# apple_all_pt1.net
KiCad netlist of a schematic drawn in EAGLE
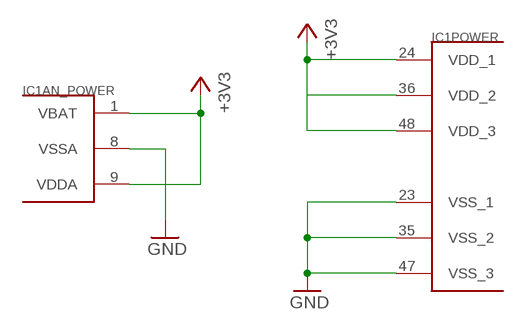
[diagram p0: schematic, sheet 1, part 1 of 2]
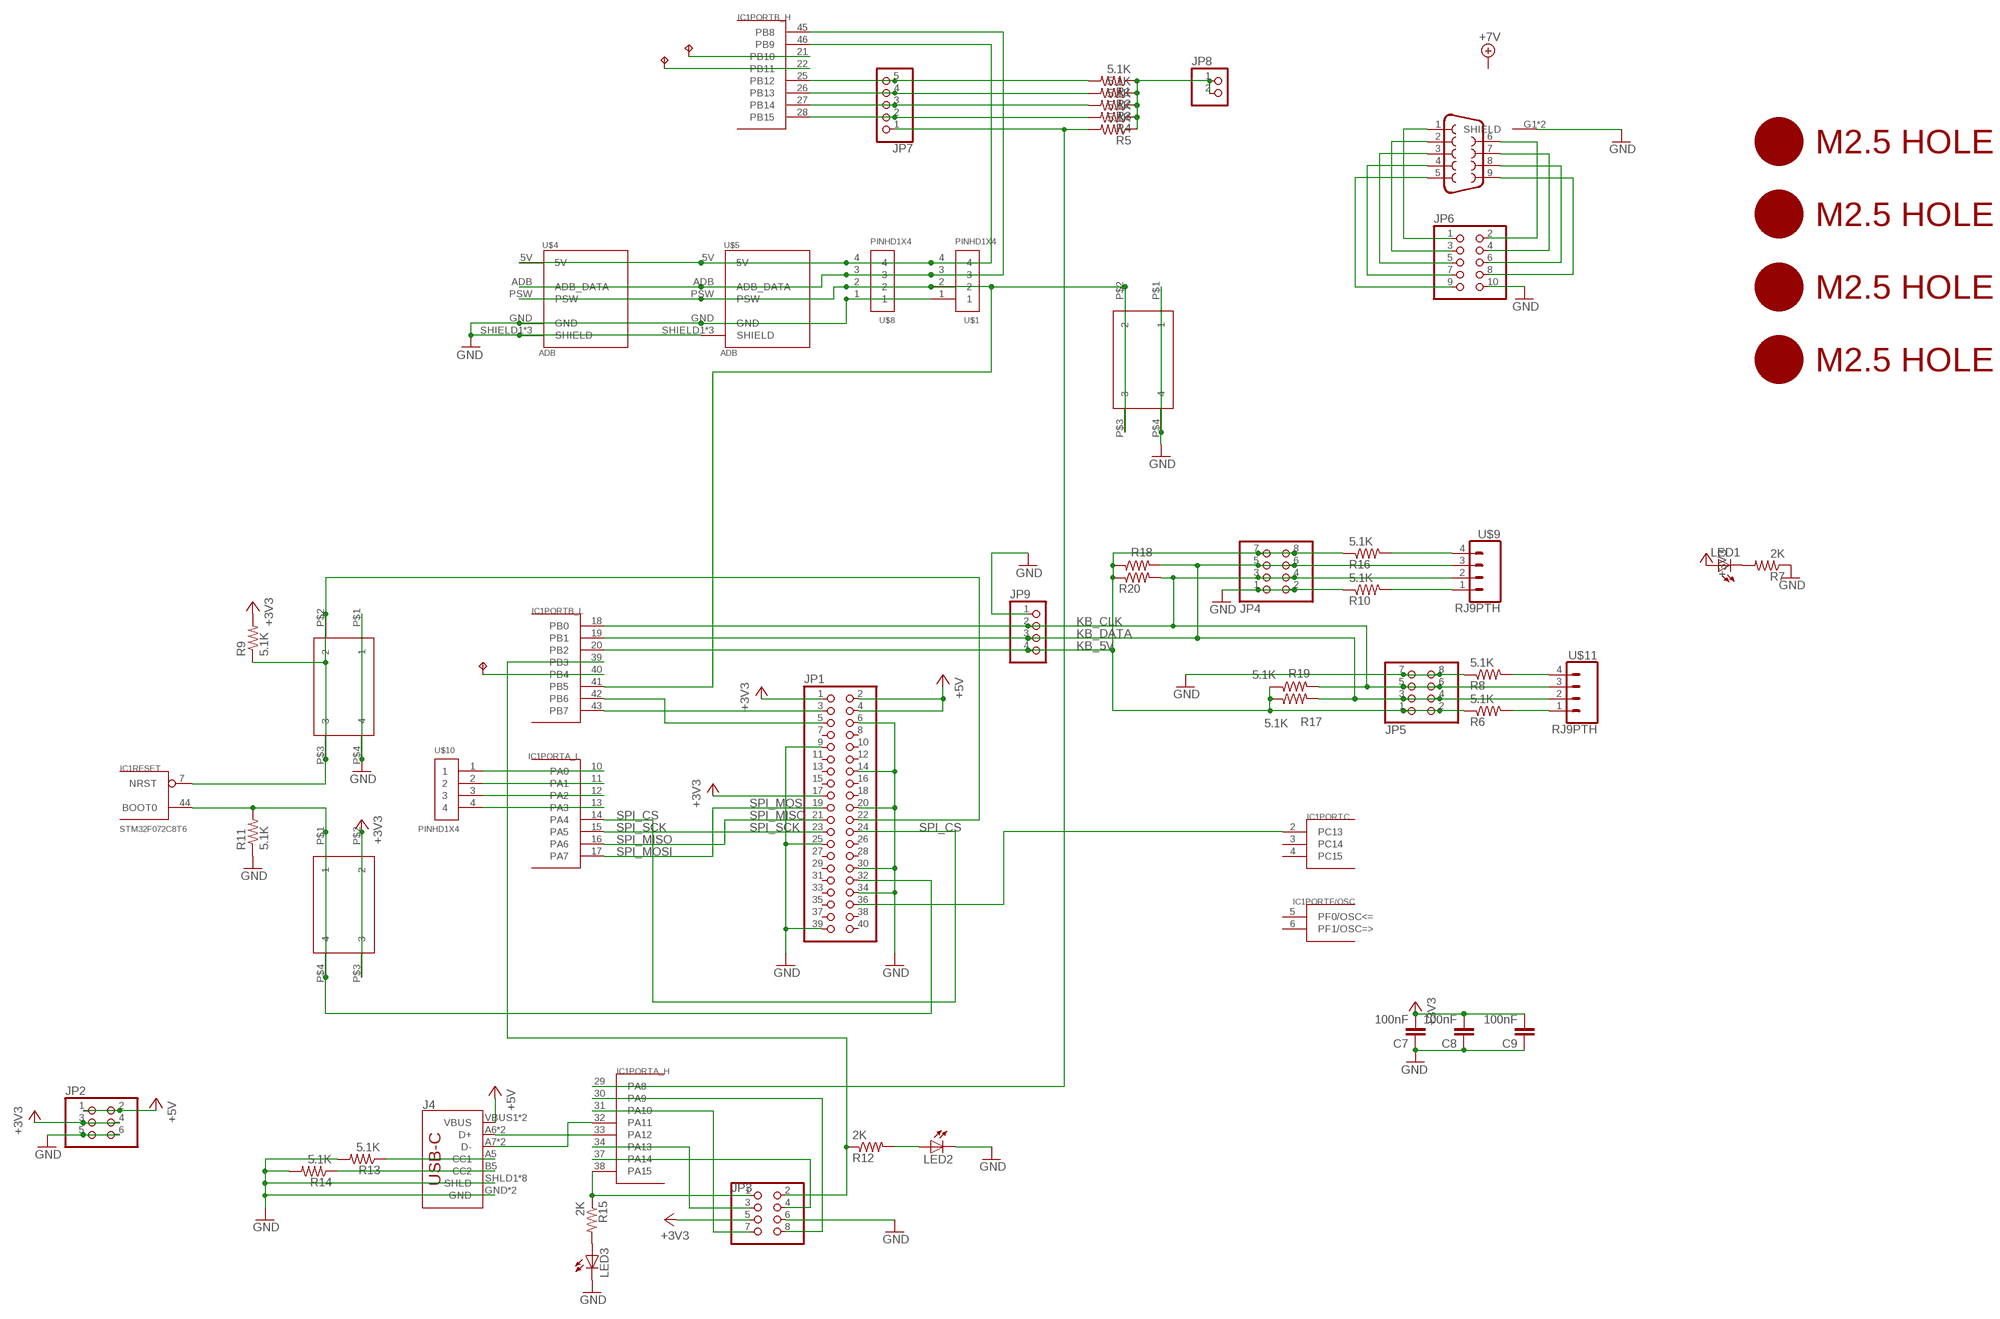
[diagram p1: schematic, sheet 1, part 2 of 2]

(export (version "E")
  (design (tool "Eeschema 10.0.6"))
  (components
    (comp (ref "C7")
      (value "100nF")
      (footprint "eagle-import:0805@1")
      (libsource (lib "eagle-import") (part "CAP0805"))
    )
    (comp (ref "C8")
      (value "100nF")
      (footprint "eagle-import:0805@1")
      (libsource (lib "eagle-import") (part "CAP0805"))
    )
    (comp (ref "C9")
      (value "100nF")
      (footprint "eagle-import:0805@1")
      (libsource (lib "eagle-import") (part "CAP0805"))
    )
    (comp (ref "IC1")
      (value "STM32F072C8T6")
      (footprint "eagle-import:TQFP48")
      (libsource (lib "eagle-import") (part "STM32F072C8T6"))
    )
    (comp (ref "J2")
      (value "DB9FEMALE")
      (footprint "eagle-import:DB9")
      (libsource (lib "eagle-import") (part "DB9FEMALE"))
    )
    (comp (ref "J4")
      (value "USB_C16PIN")
      (footprint "eagle-import:USB-C-16P")
      (libsource (lib "eagle-import") (part "USB_C16PIN"))
    )
    (comp (ref "JP1")
      (value "PINHD-2X20-BIG")
      (footprint "eagle-import:2X20-BIG")
      (libsource (lib "eagle-import") (part "PINHD-2X20-BIG"))
    )
    (comp (ref "JP2")
      (value "PINHD-2X3")
      (footprint "eagle-import:2X03")
      (libsource (lib "eagle-import") (part "PINHD-2X3"))
    )
    (comp (ref "JP3")
      (value "PINHD-2X4")
      (footprint "eagle-import:2X04")
      (libsource (lib "eagle-import") (part "PINHD-2X4"))
    )
    (comp (ref "JP4")
      (value "PINHD-2X4")
      (footprint "eagle-import:2X04")
      (libsource (lib "eagle-import") (part "PINHD-2X4"))
    )
    (comp (ref "JP5")
      (value "PINHD-2X4")
      (footprint "eagle-import:2X04")
      (libsource (lib "eagle-import") (part "PINHD-2X4"))
    )
    (comp (ref "JP6")
      (value "PINHD-2X5")
      (footprint "eagle-import:2X05")
      (libsource (lib "eagle-import") (part "PINHD-2X5"))
    )
    (comp (ref "JP7")
      (value "PINHD-1X5")
      (footprint "eagle-import:1X05")
      (libsource (lib "eagle-import") (part "PINHD-1X5"))
    )
    (comp (ref "JP8")
      (value "PINHD-1X2")
      (footprint "eagle-import:1X02")
      (libsource (lib "eagle-import") (part "PINHD-1X2"))
    )
    (comp (ref "JP9")
      (value "PINHD-1X4")
      (footprint "eagle-import:1X04")
      (libsource (lib "eagle-import") (part "PINHD-1X4"))
    )
    (comp (ref "LED1")
      (value "LEDCHIP-LED0805")
      (footprint "eagle-import:CHIP-LED0805")
      (libsource (lib "eagle-import") (part "LEDCHIP-LED0805"))
    )
    (comp (ref "LED2")
      (value "LEDCHIP-LED0805")
      (footprint "eagle-import:CHIP-LED0805")
      (libsource (lib "eagle-import") (part "LEDCHIP-LED0805"))
    )
    (comp (ref "LED3")
      (value "LEDCHIP-LED0805")
      (footprint "eagle-import:CHIP-LED0805")
      (libsource (lib "eagle-import") (part "LEDCHIP-LED0805"))
    )
    (comp (ref "R1")
      (value "5.1K")
      (footprint "eagle-import:0805")
      (libsource (lib "eagle-import") (part "RESISTOR0805-RES"))
    )
    (comp (ref "R2")
      (value "5.1K")
      (footprint "eagle-import:0805")
      (libsource (lib "eagle-import") (part "RESISTOR0805-RES"))
    )
    (comp (ref "R3")
      (value "5.1K")
      (footprint "eagle-import:0805")
      (libsource (lib "eagle-import") (part "RESISTOR0805-RES"))
    )
    (comp (ref "R4")
      (value "5.1K")
      (footprint "eagle-import:0805")
      (libsource (lib "eagle-import") (part "RESISTOR0805-RES"))
    )
    (comp (ref "R5")
      (value "5.1K")
      (footprint "eagle-import:0805")
      (libsource (lib "eagle-import") (part "RESISTOR0805-RES"))
    )
    (comp (ref "R6")
      (value "5.1K")
      (footprint "eagle-import:0805")
      (libsource (lib "eagle-import") (part "RESISTOR0805-RES"))
    )
    (comp (ref "R7")
      (value "2K")
      (footprint "eagle-import:0805")
      (libsource (lib "eagle-import") (part "RESISTOR0805-RES"))
    )
    (comp (ref "R8")
      (value "5.1K")
      (footprint "eagle-import:0805")
      (libsource (lib "eagle-import") (part "RESISTOR0805-RES"))
    )
    (comp (ref "R9")
      (value "5.1K")
      (footprint "eagle-import:0805")
      (libsource (lib "eagle-import") (part "RESISTOR0805-RES"))
    )
    (comp (ref "R10")
      (value "5.1K")
      (footprint "eagle-import:0805")
      (libsource (lib "eagle-import") (part "RESISTOR0805-RES"))
    )
    (comp (ref "R11")
      (value "5.1K")
      (footprint "eagle-import:0805")
      (libsource (lib "eagle-import") (part "RESISTOR0805-RES"))
    )
    (comp (ref "R12")
      (value "2K")
      (footprint "eagle-import:0805")
      (libsource (lib "eagle-import") (part "RESISTOR0805-RES"))
    )
    (comp (ref "R13")
      (value "5.1K")
      (footprint "eagle-import:0805")
      (libsource (lib "eagle-import") (part "RESISTOR0805-RES"))
    )
    (comp (ref "R14")
      (value "5.1K")
      (footprint "eagle-import:0805")
      (libsource (lib "eagle-import") (part "RESISTOR0805-RES"))
    )
    (comp (ref "R15")
      (value "2K")
      (footprint "eagle-import:0805")
      (libsource (lib "eagle-import") (part "RESISTOR0805-RES"))
    )
    (comp (ref "R16")
      (value "5.1K")
      (footprint "eagle-import:0805")
      (libsource (lib "eagle-import") (part "RESISTOR0805-RES"))
    )
    (comp (ref "R17")
      (value "5.1K")
      (footprint "eagle-import:0805")
      (libsource (lib "eagle-import") (part "RESISTOR0805-RES"))
    )
    (comp (ref "R18")
      (value "5.1K")
      (footprint "eagle-import:0805")
      (libsource (lib "eagle-import") (part "RESISTOR0805-RES"))
    )
    (comp (ref "R19")
      (value "5.1K")
      (footprint "eagle-import:0805")
      (libsource (lib "eagle-import") (part "RESISTOR0805-RES"))
    )
    (comp (ref "R20")
      (value "5.1K")
      (footprint "eagle-import:0805")
      (libsource (lib "eagle-import") (part "RESISTOR0805-RES"))
    )
    (comp (ref "SW1")
      (value "324_SW")
      (footprint "eagle-import:342_SWICH_FOOT")
      (libsource (lib "eagle-import") (part "324_SW"))
    )
    (comp (ref "SW2")
      (value "324_SW")
      (footprint "eagle-import:342_SWICH_FOOT")
      (libsource (lib "eagle-import") (part "324_SW"))
    )
    (comp (ref "SW3")
      (value "324_SW")
      (footprint "eagle-import:342_SWICH_FOOT")
      (libsource (lib "eagle-import") (part "324_SW"))
    )
    (comp (ref "TP1")
      (value "TPTP12R")
      (footprint "eagle-import:TP12R")
      (libsource (lib "eagle-import") (part "TPTP12R"))
    )
    (comp (ref "TP2")
      (value "TPTP12R")
      (footprint "eagle-import:TP12R")
      (libsource (lib "eagle-import") (part "TPTP12R"))
    )
    (comp (ref "TP3")
      (value "TPTP12R")
      (footprint "eagle-import:TP12R")
      (libsource (lib "eagle-import") (part "TPTP12R"))
    )
    (comp (ref "U$1")
      (value "PINHD1X4")
      (footprint "eagle-import:1X04-CLEANBIG")
      (libsource (lib "eagle-import") (part "PINHD1X4"))
    )
    (comp (ref "U$2")
      (value "M2.5HOLE")
      (footprint "eagle-import:M2.5HOLE")
      (libsource (lib "eagle-import") (part "M2.5HOLE"))
    )
    (comp (ref "U$3")
      (value "M2.5HOLE")
      (footprint "eagle-import:M2.5HOLE")
      (libsource (lib "eagle-import") (part "M2.5HOLE"))
    )
    (comp (ref "U$4")
      (value "ADB")
      (footprint "eagle-import:DIN4")
      (libsource (lib "eagle-import") (part "ADB"))
    )
    (comp (ref "U$5")
      (value "ADB")
      (footprint "eagle-import:DIN4")
      (libsource (lib "eagle-import") (part "ADB"))
    )
    (comp (ref "U$6")
      (value "M2.5HOLE")
      (footprint "eagle-import:M2.5HOLE")
      (libsource (lib "eagle-import") (part "M2.5HOLE"))
    )
    (comp (ref "U$7")
      (value "M2.5HOLE")
      (footprint "eagle-import:M2.5HOLE")
      (libsource (lib "eagle-import") (part "M2.5HOLE"))
    )
    (comp (ref "U$8")
      (value "PINHD1X4")
      (footprint "eagle-import:1X04-CLEANBIG")
      (libsource (lib "eagle-import") (part "PINHD1X4"))
    )
    (comp (ref "U$9")
      (value "RJ9PTH")
      (footprint "eagle-import:RJ9")
      (libsource (lib "eagle-import") (part "RJ9PTH"))
    )
    (comp (ref "U$10")
      (value "PINHD1X4")
      (footprint "eagle-import:1X04-CLEANBIG")
      (libsource (lib "eagle-import") (part "PINHD1X4"))
    )
    (comp (ref "U$11")
      (value "RJ9PTH")
      (footprint "eagle-import:RJ9")
      (libsource (lib "eagle-import") (part "RJ9PTH"))
    )
  )
  (nets
    (net (code "1") (name "+3V3") (class "Default")
      (node (ref "C7") (pin "2") (pinfunction "2_2") (pintype "passive"))
      (node (ref "C8") (pin "2") (pinfunction "2_2") (pintype "passive"))
      (node (ref "C9") (pin "2") (pinfunction "2_2") (pintype "passive"))
      (node (ref "IC1") (pin "1") (pinfunction "VBAT_1") (pintype "power_in"))
      (node (ref "IC1") (pin "24") (pinfunction "VDD_1_24") (pintype "power_in"))
      (node (ref "IC1") (pin "36") (pinfunction "VDD_2_36") (pintype "power_in"))
      (node (ref "IC1") (pin "48") (pinfunction "VDD_3_48") (pintype "power_in"))
      (node (ref "IC1") (pin "9") (pinfunction "VDDA_9") (pintype "power_in"))
      (node (ref "JP1") (pin "1") (pinfunction "1_1") (pintype "passive"))
      (node (ref "JP1") (pin "17") (pinfunction "17_17") (pintype "passive"))
      (node (ref "JP2") (pin "3") (pinfunction "3_3") (pintype "passive"))
      (node (ref "JP2") (pin "4") (pinfunction "4_4") (pintype "passive"))
      (node (ref "JP3") (pin "5") (pinfunction "5_5") (pintype "passive"))
      (node (ref "LED1") (pin "A") (pinfunction "A_A") (pintype "passive"))
      (node (ref "R9") (pin "2") (pinfunction "2_2") (pintype "passive"))
      (node (ref "SW2") (pin "P$2") (pinfunction "2_P$2") (pintype "bidirectional"))
      (node (ref "SW2") (pin "P$3") (pinfunction "3_P$3") (pintype "bidirectional"))
    )
    (net (code "2") (name "+5V") (class "Default")
      (node (ref "J4") (pin "VBUS1") (pinfunction "VBUS_VBUS1") (pintype "bidirectional"))
      (node (ref "J4") (pin "VBUS2") (pinfunction "VBUS_VBUS2") (pintype "bidirectional"))
      (node (ref "JP1") (pin "2") (pinfunction "2_2") (pintype "passive"))
      (node (ref "JP1") (pin "4") (pinfunction "4_4") (pintype "passive"))
      (node (ref "JP2") (pin "1") (pinfunction "1_1") (pintype "passive"))
      (node (ref "JP2") (pin "2") (pinfunction "2_2") (pintype "passive"))
    )
    (net (code "4") (name "/KB_5V") (class "Default")
      (node (ref "IC1") (pin "20") (pinfunction "PB2_20") (pintype "bidirectional"))
      (node (ref "JP4") (pin "7") (pinfunction "7_7") (pintype "passive"))
      (node (ref "JP4") (pin "8") (pinfunction "8_8") (pintype "passive"))
      (node (ref "JP5") (pin "1") (pinfunction "1_1") (pintype "passive"))
      (node (ref "JP5") (pin "2") (pinfunction "2_2") (pintype "passive"))
      (node (ref "JP9") (pin "4") (pinfunction "4_4") (pintype "passive"))
      (node (ref "R16") (pin "1") (pinfunction "1_1") (pintype "passive"))
      (node (ref "R17") (pin "1") (pinfunction "1_1") (pintype "passive"))
      (node (ref "R18") (pin "1") (pinfunction "1_1") (pintype "passive"))
      (node (ref "R19") (pin "1") (pinfunction "1_1") (pintype "passive"))
      (node (ref "R20") (pin "1") (pinfunction "1_1") (pintype "passive"))
      (node (ref "R6") (pin "1") (pinfunction "1_1") (pintype "passive"))
    )
    (net (code "5") (name "/KB_CLK") (class "Default")
      (node (ref "IC1") (pin "18") (pinfunction "PB0_18") (pintype "bidirectional"))
      (node (ref "JP4") (pin "3") (pinfunction "3_3") (pintype "passive"))
      (node (ref "JP4") (pin "4") (pinfunction "4_4") (pintype "passive"))
      (node (ref "JP5") (pin "5") (pinfunction "5_5") (pintype "passive"))
      (node (ref "JP5") (pin "6") (pinfunction "6_6") (pintype "passive"))
      (node (ref "JP9") (pin "2") (pinfunction "2_2") (pintype "passive"))
      (node (ref "R19") (pin "2") (pinfunction "2_2") (pintype "passive"))
      (node (ref "R20") (pin "2") (pinfunction "2_2") (pintype "passive"))
      (node (ref "U$11") (pin "3") (pinfunction "3_3") (pintype "passive"))
      (node (ref "U$9") (pin "2") (pinfunction "2_2") (pintype "passive"))
    )
    (net (code "6") (name "/KB_DATA") (class "Default")
      (node (ref "IC1") (pin "19") (pinfunction "PB1_19") (pintype "bidirectional"))
      (node (ref "JP4") (pin "5") (pinfunction "5_5") (pintype "passive"))
      (node (ref "JP4") (pin "6") (pinfunction "6_6") (pintype "passive"))
      (node (ref "JP5") (pin "3") (pinfunction "3_3") (pintype "passive"))
      (node (ref "JP5") (pin "4") (pinfunction "4_4") (pintype "passive"))
      (node (ref "JP9") (pin "3") (pinfunction "3_3") (pintype "passive"))
      (node (ref "R17") (pin "2") (pinfunction "2_2") (pintype "passive"))
      (node (ref "R18") (pin "2") (pinfunction "2_2") (pintype "passive"))
      (node (ref "U$11") (pin "2") (pinfunction "2_2") (pintype "passive"))
      (node (ref "U$9") (pin "3") (pinfunction "3_3") (pintype "passive"))
    )
    (net (code "7") (name "/SPI_CS") (class "Default")
      (node (ref "IC1") (pin "14") (pinfunction "PA4_14") (pintype "bidirectional"))
      (node (ref "JP1") (pin "24") (pinfunction "24_24") (pintype "passive"))
    )
    (net (code "8") (name "/SPI_MISO") (class "Default")
      (node (ref "IC1") (pin "16") (pinfunction "PA6_16") (pintype "bidirectional"))
      (node (ref "JP1") (pin "21") (pinfunction "21_21") (pintype "passive"))
    )
    (net (code "9") (name "/SPI_MOSI") (class "Default")
      (node (ref "IC1") (pin "17") (pinfunction "PA7_17") (pintype "bidirectional"))
      (node (ref "JP1") (pin "19") (pinfunction "19_19") (pintype "passive"))
    )
    (net (code "10") (name "/SPI_SCK") (class "Default")
      (node (ref "IC1") (pin "15") (pinfunction "PA5_15") (pintype "bidirectional"))
      (node (ref "JP1") (pin "23") (pinfunction "23_23") (pintype "passive"))
    )
    (net (code "11") (name "GND") (class "Default")
      (node (ref "C7") (pin "1") (pinfunction "1_1") (pintype "passive"))
      (node (ref "C8") (pin "1") (pinfunction "1_1") (pintype "passive"))
      (node (ref "C9") (pin "1") (pinfunction "1_1") (pintype "passive"))
      (node (ref "IC1") (pin "23") (pinfunction "VSS_1_23") (pintype "power_in"))
      (node (ref "IC1") (pin "35") (pinfunction "VSS_2_35") (pintype "power_in"))
      (node (ref "IC1") (pin "47") (pinfunction "VSS_3_47") (pintype "power_in"))
      (node (ref "IC1") (pin "8") (pinfunction "VSSA_8") (pintype "power_in"))
      (node (ref "J2") (pin "G1") (pinfunction "SHIELD_G1") (pintype "bidirectional"))
      (node (ref "J2") (pin "G2") (pinfunction "SHIELD_G2") (pintype "bidirectional"))
      (node (ref "J4") (pin "GND") (pinfunction "GND_GND") (pintype "bidirectional"))
      (node (ref "J4") (pin "GND2") (pinfunction "GND_GND2") (pintype "bidirectional"))
      (node (ref "J4") (pin "SHLD1") (pinfunction "SHLD_SHLD1") (pintype "bidirectional"))
      (node (ref "J4") (pin "SHLD2") (pinfunction "SHLD_SHLD2") (pintype "bidirectional"))
      (node (ref "J4") (pin "SHLD3") (pinfunction "SHLD_SHLD3") (pintype "bidirectional"))
      (node (ref "J4") (pin "SHLD4") (pinfunction "SHLD_SHLD4") (pintype "bidirectional"))
      (node (ref "J4") (pin "SHLD5") (pinfunction "SHLD_SHLD5") (pintype "bidirectional"))
      (node (ref "J4") (pin "SHLD6") (pinfunction "SHLD_SHLD6") (pintype "bidirectional"))
      (node (ref "J4") (pin "SHLD7") (pinfunction "SHLD_SHLD7") (pintype "bidirectional"))
      (node (ref "J4") (pin "SHLD8") (pinfunction "SHLD_SHLD8") (pintype "bidirectional"))
      (node (ref "JP1") (pin "14") (pinfunction "14_14") (pintype "passive"))
      (node (ref "JP1") (pin "20") (pinfunction "20_20") (pintype "passive"))
      (node (ref "JP1") (pin "25") (pinfunction "25_25") (pintype "passive"))
      (node (ref "JP1") (pin "30") (pinfunction "30_30") (pintype "passive"))
      (node (ref "JP1") (pin "34") (pinfunction "34_34") (pintype "passive"))
      (node (ref "JP1") (pin "39") (pinfunction "39_39") (pintype "passive"))
      (node (ref "JP1") (pin "6") (pinfunction "6_6") (pintype "passive"))
      (node (ref "JP1") (pin "9") (pinfunction "9_9") (pintype "passive"))
      (node (ref "JP2") (pin "5") (pinfunction "5_5") (pintype "passive"))
      (node (ref "JP2") (pin "6") (pinfunction "6_6") (pintype "passive"))
      (node (ref "JP3") (pin "6") (pinfunction "6_6") (pintype "passive"))
      (node (ref "JP4") (pin "1") (pinfunction "1_1") (pintype "passive"))
      (node (ref "JP4") (pin "2") (pinfunction "2_2") (pintype "passive"))
      (node (ref "JP5") (pin "7") (pinfunction "7_7") (pintype "passive"))
      (node (ref "JP5") (pin "8") (pinfunction "8_8") (pintype "passive"))
      (node (ref "JP6") (pin "10") (pinfunction "10_10") (pintype "passive"))
      (node (ref "JP9") (pin "1") (pinfunction "1_1") (pintype "passive"))
      (node (ref "LED2") (pin "C") (pinfunction "C_C") (pintype "passive"))
      (node (ref "LED3") (pin "C") (pinfunction "C_C") (pintype "passive"))
      (node (ref "R10") (pin "1") (pinfunction "1_1") (pintype "passive"))
      (node (ref "R11") (pin "1") (pinfunction "1_1") (pintype "passive"))
      (node (ref "R13") (pin "2") (pinfunction "2_2") (pintype "passive"))
      (node (ref "R14") (pin "2") (pinfunction "2_2") (pintype "passive"))
      (node (ref "R7") (pin "1") (pinfunction "1_1") (pintype "passive"))
      (node (ref "R8") (pin "1") (pinfunction "1_1") (pintype "passive"))
      (node (ref "SW1") (pin "P$1") (pinfunction "1_P$1") (pintype "bidirectional"))
      (node (ref "SW1") (pin "P$4") (pinfunction "4_P$4") (pintype "bidirectional"))
      (node (ref "SW3") (pin "P$1") (pinfunction "1_P$1") (pintype "bidirectional"))
      (node (ref "SW3") (pin "P$4") (pinfunction "4_P$4") (pintype "bidirectional"))
      (node (ref "U$1") (pin "1") (pinfunction "1_1") (pintype "bidirectional"))
      (node (ref "U$4") (pin "GND") (pinfunction "GND_GND") (pintype "bidirectional"))
      (node (ref "U$4") (pin "SHIELD1") (pinfunction "SHIELD_SHIELD1") (pintype "bidirectional"))
      (node (ref "U$4") (pin "SHIELD2") (pinfunction "SHIELD_SHIELD2") (pintype "bidirectional"))
      (node (ref "U$4") (pin "SHIELD3") (pinfunction "SHIELD_SHIELD3") (pintype "bidirectional"))
      (node (ref "U$5") (pin "GND") (pinfunction "GND_GND") (pintype "bidirectional"))
      (node (ref "U$5") (pin "SHIELD1") (pinfunction "SHIELD_SHIELD1") (pintype "bidirectional"))
      (node (ref "U$5") (pin "SHIELD2") (pinfunction "SHIELD_SHIELD2") (pintype "bidirectional"))
      (node (ref "U$5") (pin "SHIELD3") (pinfunction "SHIELD_SHIELD3") (pintype "bidirectional"))
      (node (ref "U$8") (pin "1") (pinfunction "1_1") (pintype "bidirectional"))
    )
    (net (code "12") (name "Net-(IC1B-PA8)") (class "Default")
      (node (ref "IC1") (pin "29") (pinfunction "PA8_29") (pintype "bidirectional"))
      (node (ref "JP7") (pin "1") (pinfunction "1_1") (pintype "passive"))
      (node (ref "R5") (pin "2") (pinfunction "2_2") (pintype "passive"))
    )
    (net (code "13") (name "Net-(IC1B-PA9)") (class "Default")
      (node (ref "IC1") (pin "30") (pinfunction "PA9_30") (pintype "bidirectional"))
      (node (ref "JP3") (pin "8") (pinfunction "8_8") (pintype "passive"))
    )
    (net (code "14") (name "Net-(IC1B-PA10)") (class "Default")
      (node (ref "IC1") (pin "31") (pinfunction "PA10_31") (pintype "bidirectional"))
      (node (ref "JP3") (pin "7") (pinfunction "7_7") (pintype "passive"))
    )
    (net (code "15") (name "Net-(IC1B-PA11)") (class "Default")
      (node (ref "IC1") (pin "32") (pinfunction "PA11_32") (pintype "bidirectional"))
      (node (ref "J4") (pin "A7") (pinfunction "D-_A7") (pintype "bidirectional"))
      (node (ref "J4") (pin "B7") (pinfunction "D-_B7") (pintype "bidirectional"))
    )
    (net (code "16") (name "Net-(IC1B-PA12)") (class "Default")
      (node (ref "IC1") (pin "33") (pinfunction "PA12_33") (pintype "bidirectional"))
      (node (ref "J4") (pin "A6") (pinfunction "D+_A6") (pintype "bidirectional"))
      (node (ref "J4") (pin "B6") (pinfunction "D+_B6") (pintype "bidirectional"))
    )
    (net (code "17") (name "Net-(IC1B-PA13)") (class "Default")
      (node (ref "IC1") (pin "34") (pinfunction "PA13_34") (pintype "bidirectional"))
      (node (ref "JP3") (pin "3") (pinfunction "3_3") (pintype "passive"))
    )
    (net (code "18") (name "Net-(IC1B-PA14)") (class "Default")
      (node (ref "IC1") (pin "37") (pinfunction "PA14_37") (pintype "bidirectional"))
      (node (ref "JP3") (pin "4") (pinfunction "4_4") (pintype "passive"))
    )
    (net (code "19") (name "Net-(IC1B-PA15)") (class "Default")
      (node (ref "IC1") (pin "38") (pinfunction "PA15_38") (pintype "bidirectional"))
      (node (ref "JP3") (pin "1") (pinfunction "1_1") (pintype "passive"))
      (node (ref "R15") (pin "1") (pinfunction "1_1") (pintype "passive"))
    )
    (net (code "20") (name "Net-(IC1C-PA0)") (class "Default")
      (node (ref "IC1") (pin "10") (pinfunction "PA0_10") (pintype "bidirectional"))
      (node (ref "U$10") (pin "1") (pinfunction "1_1") (pintype "bidirectional"))
    )
    (net (code "21") (name "Net-(IC1C-PA1)") (class "Default")
      (node (ref "IC1") (pin "11") (pinfunction "PA1_11") (pintype "bidirectional"))
      (node (ref "U$10") (pin "2") (pinfunction "2_2") (pintype "bidirectional"))
    )
    (net (code "22") (name "Net-(IC1C-PA2)") (class "Default")
      (node (ref "IC1") (pin "12") (pinfunction "PA2_12") (pintype "bidirectional"))
      (node (ref "U$10") (pin "3") (pinfunction "3_3") (pintype "bidirectional"))
    )
    (net (code "23") (name "Net-(IC1C-PA3)") (class "Default")
      (node (ref "IC1") (pin "13") (pinfunction "PA3_13") (pintype "bidirectional"))
      (node (ref "U$10") (pin "4") (pinfunction "4_4") (pintype "bidirectional"))
    )
    (net (code "24") (name "Net-(IC1D-PB8)") (class "Default")
      (node (ref "IC1") (pin "45") (pinfunction "PB8_45") (pintype "bidirectional"))
      (node (ref "U$1") (pin "3") (pinfunction "3_3") (pintype "bidirectional"))
      (node (ref "U$4") (pin "ADB") (pinfunction "ADB_DATA_ADB") (pintype "bidirectional"))
      (node (ref "U$5") (pin "ADB") (pinfunction "ADB_DATA_ADB") (pintype "bidirectional"))
      (node (ref "U$8") (pin "3") (pinfunction "3_3") (pintype "bidirectional"))
    )
    (net (code "25") (name "Net-(IC1D-PB9)") (class "Default")
      (node (ref "IC1") (pin "46") (pinfunction "PB9_46") (pintype "bidirectional"))
      (node (ref "U$1") (pin "4") (pinfunction "4_4") (pintype "bidirectional"))
      (node (ref "U$4") (pin "5V") (pinfunction "5V_5V") (pintype "bidirectional"))
      (node (ref "U$5") (pin "5V") (pinfunction "5V_5V") (pintype "bidirectional"))
      (node (ref "U$8") (pin "4") (pinfunction "4_4") (pintype "bidirectional"))
    )
    (net (code "26") (name "Net-(IC1D-PB10)") (class "Default")
      (node (ref "IC1") (pin "21") (pinfunction "PB10_21") (pintype "bidirectional"))
      (node (ref "TP1") (pin "TP") (pinfunction "TP_TP") (pintype "input"))
    )
    (net (code "27") (name "Net-(IC1D-PB11)") (class "Default")
      (node (ref "IC1") (pin "22") (pinfunction "PB11_22") (pintype "bidirectional"))
      (node (ref "TP2") (pin "TP") (pinfunction "TP_TP") (pintype "input"))
    )
    (net (code "28") (name "Net-(IC1D-PB12)") (class "Default")
      (node (ref "IC1") (pin "25") (pinfunction "PB12_25") (pintype "bidirectional"))
      (node (ref "JP7") (pin "5") (pinfunction "5_5") (pintype "passive"))
      (node (ref "R1") (pin "2") (pinfunction "2_2") (pintype "passive"))
    )
    (net (code "29") (name "Net-(IC1D-PB13)") (class "Default")
      (node (ref "IC1") (pin "26") (pinfunction "PB13_26") (pintype "bidirectional"))
      (node (ref "JP7") (pin "4") (pinfunction "4_4") (pintype "passive"))
      (node (ref "R2") (pin "2") (pinfunction "2_2") (pintype "passive"))
    )
    (net (code "30") (name "Net-(IC1D-PB14)") (class "Default")
      (node (ref "IC1") (pin "27") (pinfunction "PB14_27") (pintype "bidirectional"))
      (node (ref "JP7") (pin "3") (pinfunction "3_3") (pintype "passive"))
      (node (ref "R3") (pin "2") (pinfunction "2_2") (pintype "passive"))
    )
    (net (code "31") (name "Net-(IC1D-PB15)") (class "Default")
      (node (ref "IC1") (pin "28") (pinfunction "PB15_28") (pintype "bidirectional"))
      (node (ref "JP7") (pin "2") (pinfunction "2_2") (pintype "passive"))
      (node (ref "R4") (pin "2") (pinfunction "2_2") (pintype "passive"))
    )
    (net (code "32") (name "Net-(IC1E-PB3)") (class "Default")
      (node (ref "IC1") (pin "39") (pinfunction "PB3_39") (pintype "bidirectional"))
      (node (ref "JP3") (pin "2") (pinfunction "2_2") (pintype "passive"))
      (node (ref "R12") (pin "1") (pinfunction "1_1") (pintype "passive"))
    )
    (net (code "33") (name "Net-(IC1E-PB4)") (class "Default")
      (node (ref "IC1") (pin "40") (pinfunction "PB4_40") (pintype "bidirectional"))
      (node (ref "TP3") (pin "TP") (pinfunction "TP_TP") (pintype "input"))
    )
    (net (code "34") (name "Net-(IC1E-PB5)") (class "Default")
      (node (ref "IC1") (pin "41") (pinfunction "PB5_41") (pintype "bidirectional"))
      (node (ref "SW3") (pin "P$2") (pinfunction "2_P$2") (pintype "bidirectional"))
      (node (ref "SW3") (pin "P$3") (pinfunction "3_P$3") (pintype "bidirectional"))
      (node (ref "U$1") (pin "2") (pinfunction "2_2") (pintype "bidirectional"))
      (node (ref "U$4") (pin "PSW") (pinfunction "PSW_PSW") (pintype "bidirectional"))
      (node (ref "U$5") (pin "PSW") (pinfunction "PSW_PSW") (pintype "bidirectional"))
      (node (ref "U$8") (pin "2") (pinfunction "2_2") (pintype "bidirectional"))
    )
    (net (code "35") (name "Net-(IC1E-PB6)") (class "Default")
      (node (ref "IC1") (pin "42") (pinfunction "PB6_42") (pintype "bidirectional"))
      (node (ref "JP1") (pin "5") (pinfunction "5_5") (pintype "passive"))
    )
    (net (code "36") (name "Net-(IC1E-PB7)") (class "Default")
      (node (ref "IC1") (pin "43") (pinfunction "PB7_43") (pintype "bidirectional"))
      (node (ref "JP1") (pin "3") (pinfunction "3_3") (pintype "passive"))
    )
    (net (code "37") (name "Net-(IC1F-PC13)") (class "Default")
      (node (ref "IC1") (pin "2") (pinfunction "PC13_2") (pintype "bidirectional"))
      (node (ref "JP1") (pin "36") (pinfunction "36_36") (pintype "passive"))
    )
    (net (code "38") (name "Net-(IC1I-BOOT0)") (class "Default")
      (node (ref "IC1") (pin "44") (pinfunction "BOOT0_44") (pintype "input"))
      (node (ref "JP1") (pin "32") (pinfunction "32_32") (pintype "passive"))
      (node (ref "R11") (pin "2") (pinfunction "2_2") (pintype "passive"))
      (node (ref "SW2") (pin "P$1") (pinfunction "1_P$1") (pintype "bidirectional"))
      (node (ref "SW2") (pin "P$4") (pinfunction "4_P$4") (pintype "bidirectional"))
    )
    (net (code "39") (name "Net-(IC1I-NRST)") (class "Default")
      (node (ref "IC1") (pin "7") (pinfunction "NRST_7") (pintype "input"))
      (node (ref "JP1") (pin "22") (pinfunction "22_22") (pintype "passive"))
      (node (ref "R9") (pin "1") (pinfunction "1_1") (pintype "passive"))
      (node (ref "SW1") (pin "P$2") (pinfunction "2_P$2") (pintype "bidirectional"))
      (node (ref "SW1") (pin "P$3") (pinfunction "3_P$3") (pintype "bidirectional"))
    )
    (net (code "40") (name "Net-(J2-Pad1)") (class "Default")
      (node (ref "J2") (pin "1") (pinfunction "1_1") (pintype "passive"))
      (node (ref "JP6") (pin "1") (pinfunction "1_1") (pintype "passive"))
    )
    (net (code "41") (name "Net-(J2-Pad2)") (class "Default")
      (node (ref "J2") (pin "2") (pinfunction "2_2") (pintype "passive"))
      (node (ref "JP6") (pin "3") (pinfunction "3_3") (pintype "passive"))
    )
    (net (code "42") (name "Net-(J2-Pad3)") (class "Default")
      (node (ref "J2") (pin "3") (pinfunction "3_3") (pintype "passive"))
      (node (ref "JP6") (pin "5") (pinfunction "5_5") (pintype "passive"))
    )
    (net (code "43") (name "Net-(J2-Pad4)") (class "Default")
      (node (ref "J2") (pin "4") (pinfunction "4_4") (pintype "passive"))
      (node (ref "JP6") (pin "7") (pinfunction "7_7") (pintype "passive"))
    )
    (net (code "44") (name "Net-(J2-Pad5)") (class "Default")
      (node (ref "J2") (pin "5") (pinfunction "5_5") (pintype "passive"))
      (node (ref "JP6") (pin "9") (pinfunction "9_9") (pintype "passive"))
    )
    (net (code "45") (name "Net-(J2-Pad6)") (class "Default")
      (node (ref "J2") (pin "6") (pinfunction "6_6") (pintype "passive"))
      (node (ref "JP6") (pin "2") (pinfunction "2_2") (pintype "passive"))
    )
    (net (code "46") (name "Net-(J2-Pad7)") (class "Default")
      (node (ref "J2") (pin "7") (pinfunction "7_7") (pintype "passive"))
      (node (ref "JP6") (pin "4") (pinfunction "4_4") (pintype "passive"))
    )
    (net (code "47") (name "Net-(J2-Pad8)") (class "Default")
      (node (ref "J2") (pin "8") (pinfunction "8_8") (pintype "passive"))
      (node (ref "JP6") (pin "6") (pinfunction "6_6") (pintype "passive"))
    )
    (net (code "48") (name "Net-(J2-Pad9)") (class "Default")
      (node (ref "J2") (pin "9") (pinfunction "9_9") (pintype "passive"))
      (node (ref "JP6") (pin "8") (pinfunction "8_8") (pintype "passive"))
    )
    (net (code "49") (name "Net-(J4-CC1)") (class "Default")
      (node (ref "J4") (pin "A5") (pinfunction "CC1_A5") (pintype "bidirectional"))
      (node (ref "R13") (pin "1") (pinfunction "1_1") (pintype "passive"))
    )
    (net (code "50") (name "Net-(J4-CC2)") (class "Default")
      (node (ref "J4") (pin "B5") (pinfunction "CC2_B5") (pintype "bidirectional"))
      (node (ref "R14") (pin "1") (pinfunction "1_1") (pintype "passive"))
    )
    (net (code "51") (name "Net-(JP8-Pad1)") (class "Default")
      (node (ref "JP8") (pin "1") (pinfunction "1_1") (pintype "passive"))
      (node (ref "JP8") (pin "2") (pinfunction "2_2") (pintype "passive"))
      (node (ref "R1") (pin "1") (pinfunction "1_1") (pintype "passive"))
      (node (ref "R2") (pin "1") (pinfunction "1_1") (pintype "passive"))
      (node (ref "R3") (pin "1") (pinfunction "1_1") (pintype "passive"))
      (node (ref "R4") (pin "1") (pinfunction "1_1") (pintype "passive"))
      (node (ref "R5") (pin "1") (pinfunction "1_1") (pintype "passive"))
    )
    (net (code "52") (name "Net-(LED1-PadC)") (class "Default")
      (node (ref "LED1") (pin "C") (pinfunction "C_C") (pintype "passive"))
      (node (ref "R7") (pin "2") (pinfunction "2_2") (pintype "passive"))
    )
    (net (code "53") (name "Net-(LED2-PadA)") (class "Default")
      (node (ref "LED2") (pin "A") (pinfunction "A_A") (pintype "passive"))
      (node (ref "R12") (pin "2") (pinfunction "2_2") (pintype "passive"))
    )
    (net (code "54") (name "Net-(LED3-PadA)") (class "Default")
      (node (ref "LED3") (pin "A") (pinfunction "A_A") (pintype "passive"))
      (node (ref "R15") (pin "2") (pinfunction "2_2") (pintype "passive"))
    )
    (net (code "55") (name "Net-(R6-Pad2)") (class "Default")
      (node (ref "R6") (pin "2") (pinfunction "2_2") (pintype "passive"))
      (node (ref "U$11") (pin "1") (pinfunction "1_1") (pintype "passive"))
    )
    (net (code "56") (name "Net-(R8-Pad2)") (class "Default")
      (node (ref "R8") (pin "2") (pinfunction "2_2") (pintype "passive"))
      (node (ref "U$11") (pin "4") (pinfunction "4_4") (pintype "passive"))
    )
    (net (code "57") (name "Net-(R10-Pad2)") (class "Default")
      (node (ref "R10") (pin "2") (pinfunction "2_2") (pintype "passive"))
      (node (ref "U$9") (pin "1") (pinfunction "1_1") (pintype "passive"))
    )
    (net (code "58") (name "Net-(R16-Pad2)") (class "Default")
      (node (ref "R16") (pin "2") (pinfunction "2_2") (pintype "passive"))
      (node (ref "U$9") (pin "4") (pinfunction "4_4") (pintype "passive"))
    )
    (net (code "59") (name "unconnected-(IC1F-PC14-Pad3)") (class "Default")
      (node (ref "IC1") (pin "3") (pinfunction "PC14_3") (pintype "bidirectional"))
    )
    (net (code "60") (name "unconnected-(IC1F-PC15-Pad4)") (class "Default")
      (node (ref "IC1") (pin "4") (pinfunction "PC15_4") (pintype "bidirectional"))
    )
    (net (code "61") (name "unconnected-(IC1G-PF0{slash}OSC<=-Pad5)") (class "Default")
      (node (ref "IC1") (pin "5") (pinfunction "PF0/OSC<=_5") (pintype "bidirectional"))
    )
    (net (code "62") (name "unconnected-(IC1G-PF1{slash}OSC=>-Pad6)") (class "Default")
      (node (ref "IC1") (pin "6") (pinfunction "PF1/OSC=>_6") (pintype "bidirectional"))
    )
    (net (code "63") (name "unconnected-(JP1-Pad7)") (class "Default")
      (node (ref "JP1") (pin "7") (pinfunction "7_7") (pintype "passive"))
    )
    (net (code "64") (name "unconnected-(JP1-Pad8)") (class "Default")
      (node (ref "JP1") (pin "8") (pinfunction "8_8") (pintype "passive"))
    )
    (net (code "65") (name "unconnected-(JP1-Pad10)") (class "Default")
      (node (ref "JP1") (pin "10") (pinfunction "10_10") (pintype "passive"))
    )
    (net (code "66") (name "unconnected-(JP1-Pad11)") (class "Default")
      (node (ref "JP1") (pin "11") (pinfunction "11_11") (pintype "passive"))
    )
    (net (code "67") (name "unconnected-(JP1-Pad12)") (class "Default")
      (node (ref "JP1") (pin "12") (pinfunction "12_12") (pintype "passive"))
    )
    (net (code "68") (name "unconnected-(JP1-Pad13)") (class "Default")
      (node (ref "JP1") (pin "13") (pinfunction "13_13") (pintype "passive"))
    )
    (net (code "69") (name "unconnected-(JP1-Pad15)") (class "Default")
      (node (ref "JP1") (pin "15") (pinfunction "15_15") (pintype "passive"))
    )
    (net (code "70") (name "unconnected-(JP1-Pad16)") (class "Default")
      (node (ref "JP1") (pin "16") (pinfunction "16_16") (pintype "passive"))
    )
    (net (code "71") (name "unconnected-(JP1-Pad18)") (class "Default")
      (node (ref "JP1") (pin "18") (pinfunction "18_18") (pintype "passive"))
    )
    (net (code "72") (name "unconnected-(JP1-Pad26)") (class "Default")
      (node (ref "JP1") (pin "26") (pinfunction "26_26") (pintype "passive"))
    )
    (net (code "73") (name "unconnected-(JP1-Pad27)") (class "Default")
      (node (ref "JP1") (pin "27") (pinfunction "27_27") (pintype "passive"))
    )
    (net (code "74") (name "unconnected-(JP1-Pad28)") (class "Default")
      (node (ref "JP1") (pin "28") (pinfunction "28_28") (pintype "passive"))
    )
    (net (code "75") (name "unconnected-(JP1-Pad29)") (class "Default")
      (node (ref "JP1") (pin "29") (pinfunction "29_29") (pintype "passive"))
    )
    (net (code "76") (name "unconnected-(JP1-Pad31)") (class "Default")
      (node (ref "JP1") (pin "31") (pinfunction "31_31") (pintype "passive"))
    )
    (net (code "77") (name "unconnected-(JP1-Pad33)") (class "Default")
      (node (ref "JP1") (pin "33") (pinfunction "33_33") (pintype "passive"))
    )
    (net (code "78") (name "unconnected-(JP1-Pad35)") (class "Default")
      (node (ref "JP1") (pin "35") (pinfunction "35_35") (pintype "passive"))
    )
    (net (code "79") (name "unconnected-(JP1-Pad37)") (class "Default")
      (node (ref "JP1") (pin "37") (pinfunction "37_37") (pintype "passive"))
    )
    (net (code "80") (name "unconnected-(JP1-Pad38)") (class "Default")
      (node (ref "JP1") (pin "38") (pinfunction "38_38") (pintype "passive"))
    )
    (net (code "81") (name "unconnected-(JP1-Pad40)") (class "Default")
      (node (ref "JP1") (pin "40") (pinfunction "40_40") (pintype "passive"))
    )
  )
)
